# Methane_Sensor.net
KiCad netlist of a schematic drawn in Altium Designer
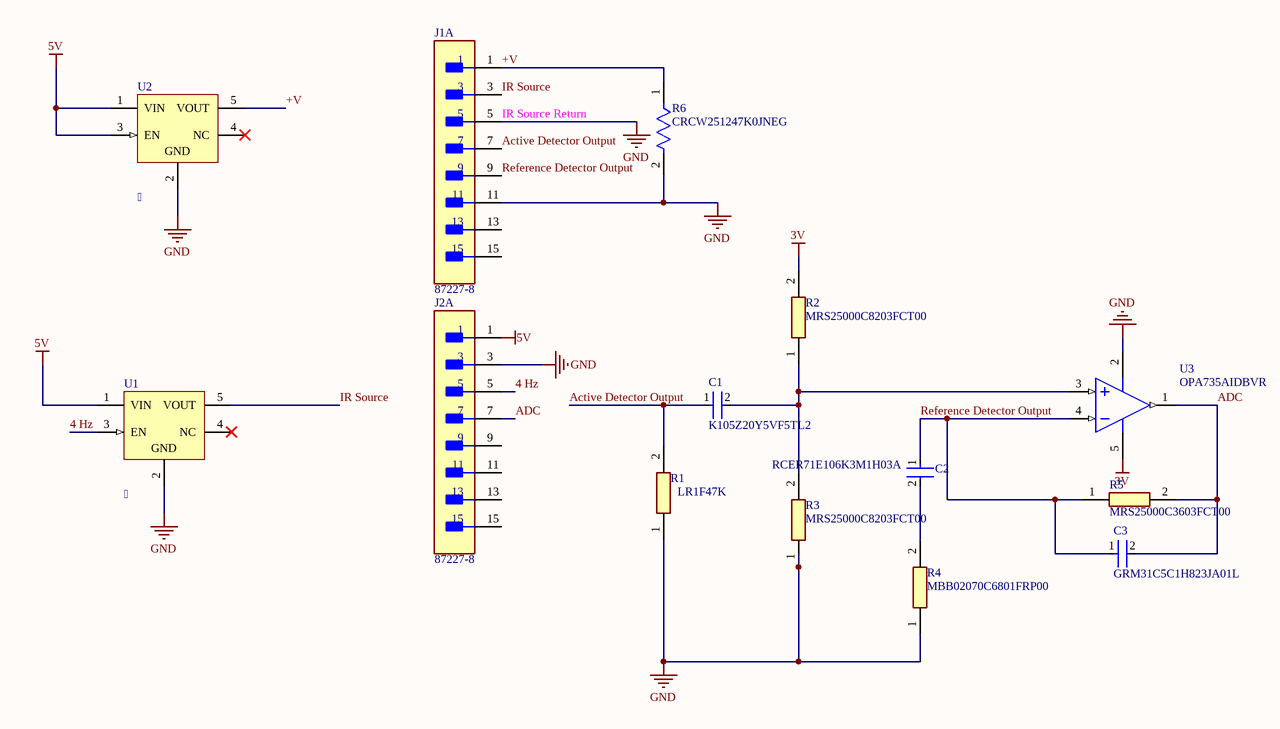
[diagram p0: Methane Sensor.SchDoc]

(export (version "E")
  (design (tool "Eeschema 10.0.6"))
  (components
    (comp (ref "C1")
      (value "K105Z20Y5VF5TL2")
      (footprint "FP-K105Z20Y5VF5TL2-MFG")
      (description "CAP CER 1UF 50V Y5V RADIAL")
      (fields
        (field (name "TOLERANCE") "-20+80%")
        (field (name "OCTOPART") "https://octopart.com/k105z20y5vf5tl2-vishay-39475252")
      )
      (libsource (lib "Altium Content Vault") (part "11868f565c42a9108669ba33697ecf6"))
    )
    (comp (ref "C2")
      (value "RCER71E106K3M1H03A")
      (footprint "FP-RCE3M1-MFG")
      (description "Cap Ceramic 10uF 25V X7R ±10% Radial 5mm +125°C Automotive Ammo Pack")
      (fields (field (name "TOLERANCE") "10%"))
      (libsource (lib "Altium Content Vault") (part "02cd4be3c70576c341d710602a673aa"))
    )
    (comp (ref "C3")
      (value "GRM31C5C1H823JA01L")
      (footprint "FP-GRM31C-0_2-e0_3_0_8-IPC_A")
      (description "Chip Multilayer Ceramic Capacitors for General Purpose, 1206, 82000pF, C0G, 30ppm/°C, 5%, 50V")
      (fields (field (name "TOLERANCE") "5%") (field (name "VOLTAGE") "50V"))
      (libsource (lib "Altium Content Vault") (part "02cd4be3c70576c341d710602a673aa"))
    )
    (comp (ref "J1")
      (value "87227-8")
      (footprint "FP-87227-8-MFG")
      (description "CONN HEADER VERT 16POS 2.54MM")
      (fields
        (field (name "MANUFACTURER") "TE Connectivity")
        (field (name "OCTOPART") "https://octopart.com/87227-8-te+connectivity-39407754")
      )
      (libsource (lib "Altium Content Vault") (part "4b6d22b45e2f925f038cba5d936fbcc"))
    )
    (comp (ref "J2")
      (value "87227-8")
      (footprint "FP-87227-8-MFG")
      (description "CONN HEADER VERT 16POS 2.54MM")
      (fields
        (field (name "MANUFACTURER") "TE Connectivity")
        (field (name "OCTOPART") "https://octopart.com/87227-8-te+connectivity-39407754")
      )
      (libsource (lib "Altium Content Vault") (part "4b6d22b45e2f925f038cba5d936fbcc"))
    )
    (comp (ref "R1")
      (value "LR1F47K")
      (footprint "SamacSys:RESAD1540W55L620D230")
      (description "Resistor")
      (fields (field (name "MOUSER PART NUMBER") "279-LR1F47K"))
      (libsource (lib "*") (part "LR1F47K"))
    )
    (comp (ref "R2")
      (value "MRS25000C8203FCT00")
      (footprint "SamacSys:RESAD1650W60L650D250")
      (description "Resistor")
      (libsource (lib "*") (part "MRS25000C8203FCT00"))
    )
    (comp (ref "R3")
      (value "MRS25000C8203FCT00")
      (footprint "SamacSys:RESAD1650W60L650D250")
      (description "Resistor")
      (libsource (lib "*") (part "MRS25000C8203FCT00"))
    )
    (comp (ref "R4")
      (value "MBB02070C6801FRP00")
      (footprint "SamacSys:RESAD1650W60L650D250")
      (description "Resistor")
      (fields (field (name "MOUSER PART NUMBER") "594-MBB02070C6801FRP"))
      (libsource (lib "*") (part "MBB02070C6801FRP00"))
    )
    (comp (ref "R5")
      (value "MRS25000C3603FCT00")
      (footprint "SamacSys:RESAD1650W60L650D250")
      (description "Resistor")
      (libsource (lib "*") (part "MRS25000C3603FCT00"))
    )
    (comp (ref "R6")
      (value "CRCW251247K0JNEG")
      (footprint "FP-CRCW2512-e3-IPC_A")
      (description "RES Thick Film, 47kΩ, 5%, 1W, 200ppm/°C, 2512")
      (fields (field (name "TOLERANCE") "5%"))
      (libsource (lib "Altium Content Vault") (part "1029c3af85768c4190bb7ad29bc67b5"))
    )
    (comp (ref "U1")
      (value "")
      (footprint "ADI-UJ-5_M")
      (fields (field (name "PARTNUMBER") "ADP122AUJZ-3.0-R7") (field (name "MANUFACTURER") "Analog Devices"))
      (libsource (lib "Altium Content Vault") (part "ADI-ADP1XX-UJ-5"))
    )
    (comp (ref "U2")
      (value "")
      (footprint "ADI-UJ-5_M")
      (fields (field (name "PARTNUMBER") "ADP122AUJZ-3.0-R7") (field (name "MANUFACTURER") "Analog Devices"))
      (libsource (lib "Altium Content Vault") (part "ADI-ADP1XX-UJ-5"))
    )
    (comp (ref "U3")
      (value "OPA735AIDBVR")
      (footprint "DBV0005A_N")
      (fields (field (name "MANUFACTURER") "Texas Instruments"))
      (libsource (lib "Altium Content Vault") (part "TI-OPA_SM7XXXX-DBV5"))
    )
  )
  (nets
    (net (code "1") (name "/+V") (class "Default")
      (node (ref "J1") (pin "1") (pinfunction "1_1") (pintype "passive"))
      (node (ref "R6") (pin "1") (pinfunction "1_1") (pintype "passive"))
      (node (ref "U2") (pin "5") (pinfunction "VOUT_5") (pintype "power_in"))
    )
    (net (code "2") (name "/4 Hz") (class "Default")
      (node (ref "J2") (pin "5") (pinfunction "5_5") (pintype "passive"))
      (node (ref "U1") (pin "3") (pinfunction "EN_3") (pintype "input"))
    )
    (net (code "3") (name "/ADC") (class "Default")
      (node (ref "C3") (pin "2") (pinfunction "2_2") (pintype "passive"))
      (node (ref "J2") (pin "7") (pinfunction "7_7") (pintype "passive"))
      (node (ref "R5") (pin "2") (pinfunction "2_2") (pintype "passive"))
      (node (ref "U3") (pin "1") (pinfunction "OUT_1") (pintype "output"))
    )
    (net (code "4") (name "/Active Detector Output") (class "Default")
      (node (ref "C1") (pin "1") (pinfunction "1_1") (pintype "passive"))
      (node (ref "J1") (pin "7") (pinfunction "7_7") (pintype "passive"))
      (node (ref "R1") (pin "2") (pinfunction "2_2") (pintype "passive"))
    )
    (net (code "5") (name "/IR Source") (class "Default")
      (node (ref "J1") (pin "3") (pinfunction "3_3") (pintype "passive"))
      (node (ref "U1") (pin "5") (pinfunction "VOUT_5") (pintype "power_in"))
    )
    (net (code "6") (name "/Reference Detector Output") (class "Default")
      (node (ref "C2") (pin "1") (pinfunction "1_1") (pintype "passive"))
      (node (ref "C3") (pin "1") (pinfunction "1_1") (pintype "passive"))
      (node (ref "J1") (pin "9") (pinfunction "9_9") (pintype "passive"))
      (node (ref "R5") (pin "1") (pinfunction "1_1") (pintype "passive"))
      (node (ref "U3") (pin "4") (pinfunction "IN-_4") (pintype "input"))
    )
    (net (code "7") (name "3V") (class "Default")
      (node (ref "R2") (pin "2") (pinfunction "2_2") (pintype "passive"))
      (node (ref "U3") (pin "5") (pinfunction "V+_5") (pintype "power_in"))
    )
    (net (code "8") (name "5V") (class "Default")
      (node (ref "J2") (pin "1") (pinfunction "1_1") (pintype "passive"))
      (node (ref "U1") (pin "1") (pinfunction "VIN_1") (pintype "power_in"))
      (node (ref "U2") (pin "1") (pinfunction "VIN_1") (pintype "power_in"))
      (node (ref "U2") (pin "3") (pinfunction "EN_3") (pintype "input"))
    )
    (net (code "9") (name "GND") (class "Default")
      (node (ref "J1") (pin "11") (pinfunction "11_11") (pintype "passive"))
      (node (ref "J1") (pin "5") (pinfunction "5_5") (pintype "passive"))
      (node (ref "J2") (pin "3") (pinfunction "3_3") (pintype "passive"))
      (node (ref "R1") (pin "1") (pinfunction "1_1") (pintype "passive"))
      (node (ref "R3") (pin "1") (pinfunction "1_1") (pintype "passive"))
      (node (ref "R4") (pin "1") (pinfunction "1_1") (pintype "passive"))
      (node (ref "R6") (pin "2") (pinfunction "2_2") (pintype "passive"))
      (node (ref "U1") (pin "2") (pinfunction "GND_2") (pintype "power_in"))
      (node (ref "U2") (pin "2") (pinfunction "GND_2") (pintype "power_in"))
      (node (ref "U3") (pin "2") (pinfunction "V-_2") (pintype "power_in"))
    )
    (net (code "10") (name "Net-(C2-Pad2)") (class "Default")
      (node (ref "C2") (pin "2") (pinfunction "2_2") (pintype "passive"))
      (node (ref "R4") (pin "2") (pinfunction "2_2") (pintype "passive"))
    )
    (net (code "11") (name "Net-(U3-IN+)") (class "Default")
      (node (ref "C1") (pin "2") (pinfunction "2_2") (pintype "passive"))
      (node (ref "R2") (pin "1") (pinfunction "1_1") (pintype "passive"))
      (node (ref "R3") (pin "2") (pinfunction "2_2") (pintype "passive"))
      (node (ref "U3") (pin "3") (pinfunction "IN+_3") (pintype "input"))
    )
    (net (code "12") (name "unconnected-(J1-Pad13)") (class "Default")
      (node (ref "J1") (pin "13") (pinfunction "13_13") (pintype "passive"))
    )
    (net (code "13") (name "unconnected-(J1-Pad15)") (class "Default")
      (node (ref "J1") (pin "15") (pinfunction "15_15") (pintype "passive"))
    )
    (net (code "14") (name "unconnected-(J2-Pad9)") (class "Default")
      (node (ref "J2") (pin "9") (pinfunction "9_9") (pintype "passive"))
    )
    (net (code "15") (name "unconnected-(J2-Pad11)") (class "Default")
      (node (ref "J2") (pin "11") (pinfunction "11_11") (pintype "passive"))
    )
    (net (code "16") (name "unconnected-(J2-Pad13)") (class "Default")
      (node (ref "J2") (pin "13") (pinfunction "13_13") (pintype "passive"))
    )
    (net (code "17") (name "unconnected-(J2-Pad15)") (class "Default")
      (node (ref "J2") (pin "15") (pinfunction "15_15") (pintype "passive"))
    )
    (net (code "18") (name "unconnected-(U1-NC-Pad4)") (class "Default")
      (node (ref "U1") (pin "4") (pinfunction "NC_4") (pintype "passive+no_connect"))
    )
    (net (code "19") (name "unconnected-(U2-NC-Pad4)") (class "Default")
      (node (ref "U2") (pin "4") (pinfunction "NC_4") (pintype "passive+no_connect"))
    )
  )
)
